# SCH_Hacker-Card_2025-03-16.net
KiCad netlist of a schematic drawn in EasyEDA
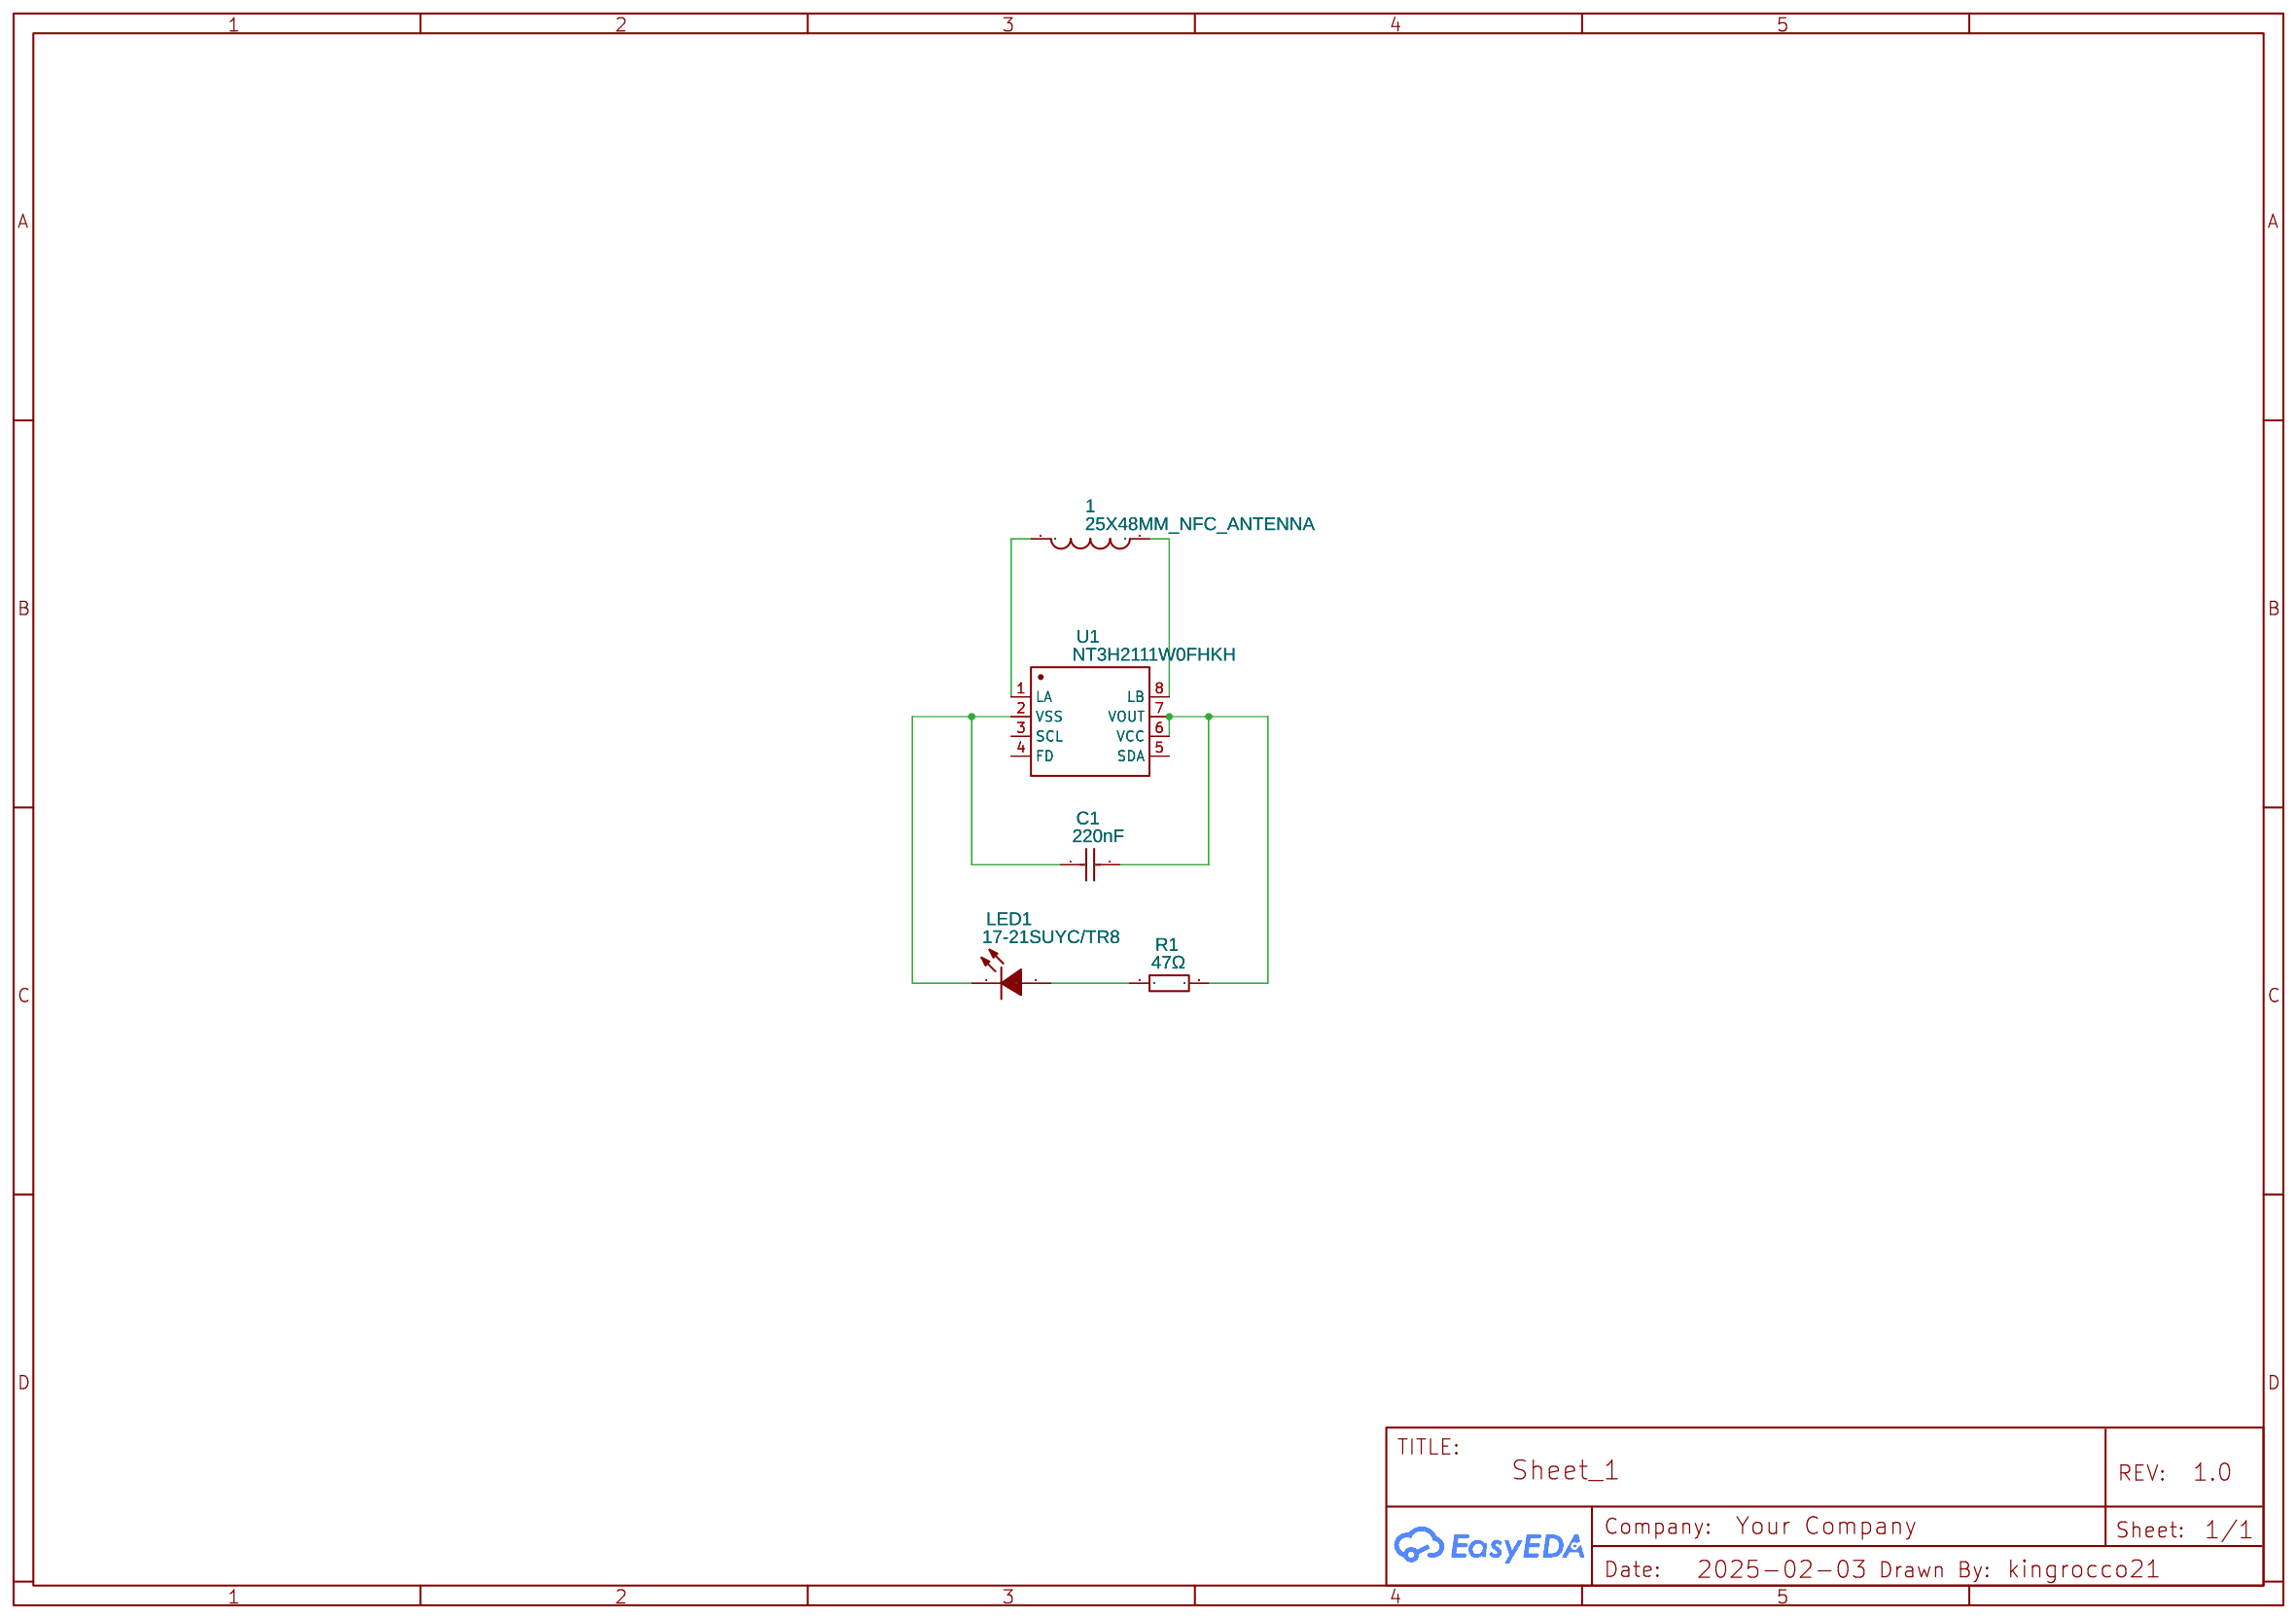
[diagram p0: schematic sheet]

(export (version "E")
  (design (tool "Eeschema 10.0.6"))
  (components
    (comp (ref "1") (value "25X48MM_NFC_ANTENNA") (libsource (lib "") (part "25X48MM_NFC_ANTENNA")))
    (comp (ref "C1")
      (value "220nF")
      (fields
        (field (name "Manufacturer Part") "CL10B224KA8NNNC")
        (field (name "Manufacturer") "SAMSUNG(三星)")
      )
      (libsource (lib "") (part "CL10B224KA8NNNC"))
    )
    (comp (ref "LED1")
      (value "17-21SUYC/TR8")
      (fields (field (name "Manufacturer Part") "KT-0805黄灯") (field (name "Manufacturer") "KENTO"))
      (libsource (lib "") (part "17-21SUYC/TR8"))
    )
    (comp (ref "R1")
      (value "47Ω")
      (fields
        (field (name "Manufacturer Part") "0603WAF470JT5E")
        (field (name "Manufacturer") "UNI-ROYAL(厚声)")
      )
      (libsource (lib "") (part "0603WAF470JT5E"))
    )
    (comp (ref "U1")
      (value "NT3H2111W0FHKH")
      (fields (field (name "Manufacturer") "NXP(恩智浦)"))
      (libsource (lib "") (part "NT3H2111W0FHKH"))
    )
  )
  (nets
    (net (code "1") (name "Net-(LED1-+)") (class "Default")
      (node (ref "LED1") (pin "1") (pinfunction "+_1") (pintype "unspecified"))
      (node (ref "R1") (pin "1") (pinfunction "1_1") (pintype "input"))
    )
    (net (code "2") (name "Net-(LED1--)") (class "Default")
      (node (ref "C1") (pin "1") (pinfunction "1_1") (pintype "input"))
      (node (ref "LED1") (pin "2") (pinfunction "-_2") (pintype "unspecified"))
      (node (ref "U1") (pin "2") (pinfunction "VSS_2") (pintype "unspecified"))
    )
    (net (code "3") (name "Net-(U1-LA)") (class "Default")
      (node (ref "1") (pin "P$2") (pinfunction "P$2_P$2") (pintype "bidirectional"))
      (node (ref "U1") (pin "1") (pinfunction "LA_1") (pintype "unspecified"))
    )
    (net (code "4") (name "Net-(U1-LB)") (class "Default")
      (node (ref "1") (pin "P$1") (pinfunction "P$1_P$1") (pintype "bidirectional"))
      (node (ref "U1") (pin "8") (pinfunction "LB_8") (pintype "unspecified"))
    )
    (net (code "5") (name "Net-(U1-VCC)") (class "Default")
      (node (ref "C1") (pin "2") (pinfunction "2_2") (pintype "input"))
      (node (ref "R1") (pin "2") (pinfunction "2_2") (pintype "input"))
      (node (ref "U1") (pin "6") (pinfunction "VCC_6") (pintype "unspecified"))
      (node (ref "U1") (pin "7") (pinfunction "VOUT_7") (pintype "unspecified"))
    )
    (net (code "6") (name "unconnected-(U1-FD-Pad4)") (class "Default")
      (node (ref "U1") (pin "4") (pinfunction "FD_4") (pintype "unspecified"))
    )
    (net (code "7") (name "unconnected-(U1-SCL-Pad3)") (class "Default")
      (node (ref "U1") (pin "3") (pinfunction "SCL_3") (pintype "unspecified"))
    )
    (net (code "8") (name "unconnected-(U1-SDA-Pad5)") (class "Default")
      (node (ref "U1") (pin "5") (pinfunction "SDA_5") (pintype "unspecified"))
    )
  )
)
